# Power_Delivery.net
KiCad netlist of a schematic drawn in Altium Designer
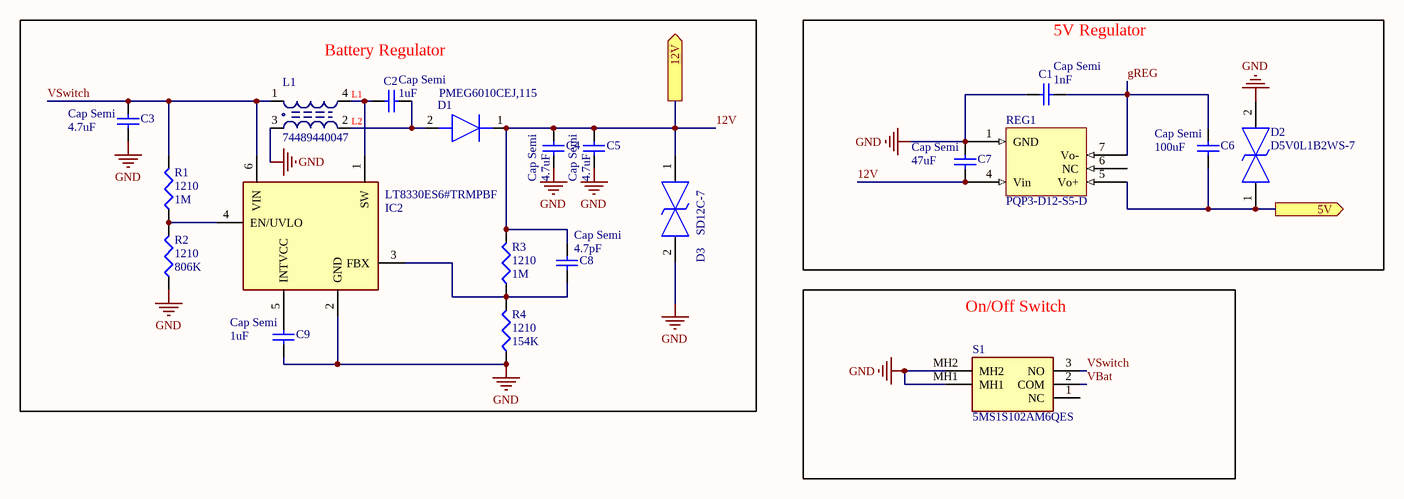
[diagram p0: Power Delivery.SchDoc]

(export (version "E")
  (design (tool "Eeschema 10.0.6"))
  (components
    (comp (ref "C1")
      (value "Cap Semi")
      (footprint "C1210")
      (description "Capacitor (Semiconductor SIM Model)")
      (fields (field (name "ALTIUM_VALUE") "1nF") (field (name "PUBLISHER") "Altium Limited"))
      (libsource (lib "Miscellaneous Devices") (part "Cap Semi"))
    )
    (comp (ref "C2")
      (value "Cap Semi")
      (footprint "C1210")
      (description "Capacitor (Semiconductor SIM Model)")
      (fields (field (name "ALTIUM_VALUE") "1uF") (field (name "PUBLISHER") "Altium Limited"))
      (libsource (lib "Miscellaneous Devices") (part "Cap Semi"))
    )
    (comp (ref "C3")
      (value "Cap Semi")
      (footprint "C1210")
      (description "Capacitor (Semiconductor SIM Model)")
      (fields (field (name "ALTIUM_VALUE") "4.7uF") (field (name "PUBLISHER") "Altium Limited"))
      (libsource (lib "Miscellaneous Devices") (part "Cap Semi"))
    )
    (comp (ref "C4")
      (value "Cap Semi")
      (footprint "C1210")
      (description "Capacitor (Semiconductor SIM Model)")
      (fields (field (name "ALTIUM_VALUE") "4.7uF") (field (name "PUBLISHER") "Altium Limited"))
      (libsource (lib "Miscellaneous Devices") (part "Cap Semi"))
    )
    (comp (ref "C5")
      (value "Cap Semi")
      (footprint "C1210")
      (description "Capacitor (Semiconductor SIM Model)")
      (fields (field (name "ALTIUM_VALUE") "4.7uF") (field (name "PUBLISHER") "Altium Limited"))
      (libsource (lib "Miscellaneous Devices") (part "Cap Semi"))
    )
    (comp (ref "C6")
      (value "Cap Semi")
      (footprint "C1210")
      (description "Capacitor (Semiconductor SIM Model)")
      (fields (field (name "ALTIUM_VALUE") "100uF") (field (name "PUBLISHER") "Altium Limited"))
      (libsource (lib "Miscellaneous Devices") (part "Cap Semi"))
    )
    (comp (ref "C7")
      (value "Cap Semi")
      (footprint "C1210")
      (description "Capacitor (Semiconductor SIM Model)")
      (fields (field (name "ALTIUM_VALUE") "47uF") (field (name "PUBLISHER") "Altium Limited"))
      (libsource (lib "Miscellaneous Devices") (part "Cap Semi"))
    )
    (comp (ref "C8")
      (value "Cap Semi")
      (footprint "C1210")
      (description "Capacitor (Semiconductor SIM Model)")
      (fields (field (name "ALTIUM_VALUE") "4.7pF") (field (name "PUBLISHER") "Altium Limited"))
      (libsource (lib "Miscellaneous Devices") (part "Cap Semi"))
    )
    (comp (ref "C9")
      (value "Cap Semi")
      (footprint "C1210")
      (description "Capacitor (Semiconductor SIM Model)")
      (fields (field (name "ALTIUM_VALUE") "1uF") (field (name "PUBLISHER") "Altium Limited"))
      (libsource (lib "Miscellaneous Devices") (part "Cap Semi"))
    )
    (comp (ref "D1")
      (value "PMEG6010CEJ,115")
      (footprint "SamacSys:SODFL2512X80N")
      (description "Diode")
      (fields (field (name "MOUSER PART NUMBER") "771-PMEG6010CEJ-T/R"))
      (libsource (lib "*") (part "PMEG6010CEJ,115"))
    )
    (comp (ref "D2")
      (value "D5V0L1B2WS-7")
      (footprint "D5V0L1B2WS7")
      (description "TVS Diode (Bi-directional)")
      (fields (field (name "MOUSER PART NUMBER") "621-D5V0L1B2WS-7"))
      (libsource (lib "*") (part "D5V0L1B2WS-7"))
    )
    (comp (ref "D3")
      (value "SD12C-7")
      (footprint "SamacSys:SD12C7")
      (description "TVS Diode (Bi-directional)")
      (fields (field (name "MOUSER PART NUMBER") "621-SD12C-7"))
      (libsource (lib "*") (part "SD12C-7"))
    )
    (comp (ref "IC2")
      (value "LT8330ES6#TRMPBF")
      (footprint "SamacSys:SOT95P280X100-6N")
      (description "Integrated Circuit")
      (fields (field (name "MOUSER PART NUMBER") "584-LT8330ES6#TRMPBF"))
      (libsource (lib "SamacSys") (part "LT8330ES6#TRMPBF"))
    )
    (comp (ref "L1")
      (value "74489440047")
      (footprint "WE-TDC 8038")
      (description "SMD Shielded Coupled Inductor WE-TDC, L=4.7 µH")
      (fields (field (name "MANUFACTURER") "Wuerth Elektronik"))
      (libsource (lib "Altium Content Vault") (part "WE-IND-INDUCTOR-4H"))
    )
    (comp (ref "R1")
      (value "1210")
      (footprint "14-1210")
      (description "Resistor")
      (fields (field (name "ALTIUM_VALUE") "1M") (field (name "PUBLISHER") "Altium Limited"))
      (libsource (lib "Miscellaneous Devices") (part "Res3"))
    )
    (comp (ref "R2")
      (value "1210")
      (footprint "14-1210")
      (description "Resistor")
      (fields (field (name "ALTIUM_VALUE") "806K") (field (name "PUBLISHER") "Altium Limited"))
      (libsource (lib "Miscellaneous Devices") (part "Res3"))
    )
    (comp (ref "R3")
      (value "1210")
      (footprint "14-1210")
      (description "Resistor")
      (fields (field (name "ALTIUM_VALUE") "1M") (field (name "PUBLISHER") "Altium Limited"))
      (libsource (lib "Miscellaneous Devices") (part "Res3"))
    )
    (comp (ref "R4")
      (value "1210")
      (footprint "14-1210")
      (description "Resistor")
      (fields (field (name "ALTIUM_VALUE") "154K") (field (name "PUBLISHER") "Altium Limited"))
      (libsource (lib "Miscellaneous Devices") (part "Res3"))
    )
    (comp (ref "REG1")
      (value "PQP3-D12-S5-D")
      (footprint "PQP3-D12-S5-D-Footprint-1")
      (description "Module DC-DC 12VIN 1-OUT 5V 0.6A 3W 5-Pin DIP Module Tube")
      (libsource (lib "Jouveer") (part "PQP3-D12-S5-D"))
    )
    (comp (ref "S1")
      (value "5MS1S102AM6QES")
      (footprint "SamacSys:5MS1S102AM6QES")
      (description "Switch")
      (fields (field (name "MOUSER PART NUMBER") "118-5MS1S102AM6QES"))
      (libsource (lib "*") (part "5MS1S102AM6QES"))
    )
  )
  (nets
    (net (code "1") (name "/5V") (class "Default")
      (node (ref "C6") (pin "1") (pinfunction "1_1") (pintype "passive"))
      (node (ref "D2") (pin "1") (pinfunction "1_1") (pintype "passive"))
      (node (ref "REG1") (pin "5") (pinfunction "Vo+_5") (pintype "input"))
    )
    (net (code "2") (name "/12V") (class "Default")
      (node (ref "C4") (pin "2") (pinfunction "2_2") (pintype "passive"))
      (node (ref "C5") (pin "2") (pinfunction "2_2") (pintype "passive"))
      (node (ref "C7") (pin "1") (pinfunction "1_1") (pintype "passive"))
      (node (ref "C8") (pin "2") (pinfunction "2_2") (pintype "passive"))
      (node (ref "D1") (pin "1") (pinfunction "K_1") (pintype "passive"))
      (node (ref "D3") (pin "1") (pinfunction "1_1") (pintype "passive"))
      (node (ref "R3") (pin "2") (pinfunction "2_2") (pintype "passive"))
      (node (ref "REG1") (pin "4") (pinfunction "Vin_4") (pintype "input"))
    )
    (net (code "3") (name "/VBat") (class "Default")
      (node (ref "S1") (pin "2") (pinfunction "COM_2") (pintype "passive"))
    )
    (net (code "4") (name "/VSwitch") (class "Default")
      (node (ref "C3") (pin "2") (pinfunction "2_2") (pintype "passive"))
      (node (ref "IC2") (pin "6") (pinfunction "VIN_6") (pintype "passive"))
      (node (ref "L1") (pin "1") (pinfunction "1_1") (pintype "passive"))
      (node (ref "R1") (pin "2") (pinfunction "2_2") (pintype "passive"))
      (node (ref "S1") (pin "3") (pinfunction "NO_3") (pintype "passive"))
    )
    (net (code "5") (name "/gREG") (class "Default")
      (node (ref "C1") (pin "2") (pinfunction "2_2") (pintype "passive"))
      (node (ref "C6") (pin "2") (pinfunction "2_2") (pintype "passive"))
      (node (ref "REG1") (pin "7") (pinfunction "Vo-_7") (pintype "input"))
    )
    (net (code "6") (name "GND") (class "Default")
      (node (ref "C1") (pin "1") (pinfunction "1_1") (pintype "passive"))
      (node (ref "C3") (pin "1") (pinfunction "1_1") (pintype "passive"))
      (node (ref "C4") (pin "1") (pinfunction "1_1") (pintype "passive"))
      (node (ref "C5") (pin "1") (pinfunction "1_1") (pintype "passive"))
      (node (ref "C7") (pin "2") (pinfunction "2_2") (pintype "passive"))
      (node (ref "C9") (pin "1") (pinfunction "1_1") (pintype "passive"))
      (node (ref "D2") (pin "2") (pinfunction "2_2") (pintype "passive"))
      (node (ref "D3") (pin "2") (pinfunction "2_2") (pintype "passive"))
      (node (ref "IC2") (pin "2") (pinfunction "GND_2") (pintype "passive"))
      (node (ref "L1") (pin "3") (pinfunction "3_3") (pintype "passive"))
      (node (ref "R2") (pin "1") (pinfunction "1_1") (pintype "passive"))
      (node (ref "R4") (pin "1") (pinfunction "1_1") (pintype "passive"))
      (node (ref "REG1") (pin "1") (pinfunction "GND_1") (pintype "input"))
      (node (ref "S1") (pin "MH1") (pinfunction "MH1_MH1") (pintype "passive"))
      (node (ref "S1") (pin "MH2") (pinfunction "MH2_MH2") (pintype "passive"))
    )
    (net (code "7") (name "Net-(D1-A)") (class "Default")
      (node (ref "C2") (pin "2") (pinfunction "2_2") (pintype "passive"))
      (node (ref "D1") (pin "2") (pinfunction "A_2") (pintype "passive"))
      (node (ref "L1") (pin "2") (pinfunction "2_2") (pintype "passive"))
    )
    (net (code "8") (name "Net-(IC2-EN{slash}UVLO)") (class "Default")
      (node (ref "IC2") (pin "4") (pinfunction "EN/UVLO_4") (pintype "passive"))
      (node (ref "R1") (pin "1") (pinfunction "1_1") (pintype "passive"))
      (node (ref "R2") (pin "2") (pinfunction "2_2") (pintype "passive"))
    )
    (net (code "9") (name "Net-(IC2-FBX)") (class "Default")
      (node (ref "C8") (pin "1") (pinfunction "1_1") (pintype "passive"))
      (node (ref "IC2") (pin "3") (pinfunction "FBX_3") (pintype "passive"))
      (node (ref "R3") (pin "1") (pinfunction "1_1") (pintype "passive"))
      (node (ref "R4") (pin "2") (pinfunction "2_2") (pintype "passive"))
    )
    (net (code "10") (name "Net-(IC2-INTVCC)") (class "Default")
      (node (ref "C9") (pin "2") (pinfunction "2_2") (pintype "passive"))
      (node (ref "IC2") (pin "5") (pinfunction "INTVCC_5") (pintype "passive"))
    )
    (net (code "11") (name "Net-(IC2-SW)") (class "Default")
      (node (ref "C2") (pin "1") (pinfunction "1_1") (pintype "passive"))
      (node (ref "IC2") (pin "1") (pinfunction "SW_1") (pintype "passive"))
      (node (ref "L1") (pin "4") (pinfunction "4_4") (pintype "passive"))
    )
    (net (code "12") (name "unconnected-(REG1-NC-Pad6)") (class "Default")
      (node (ref "REG1") (pin "6") (pinfunction "NC_6") (pintype "input"))
    )
    (net (code "13") (name "unconnected-(S1-NC-Pad1)") (class "Default")
      (node (ref "S1") (pin "1") (pinfunction "NC_1") (pintype "passive"))
    )
  )
)
